# WD1M_BTLE_JDY-08.net
KiCad netlist of a schematic drawn in EAGLE
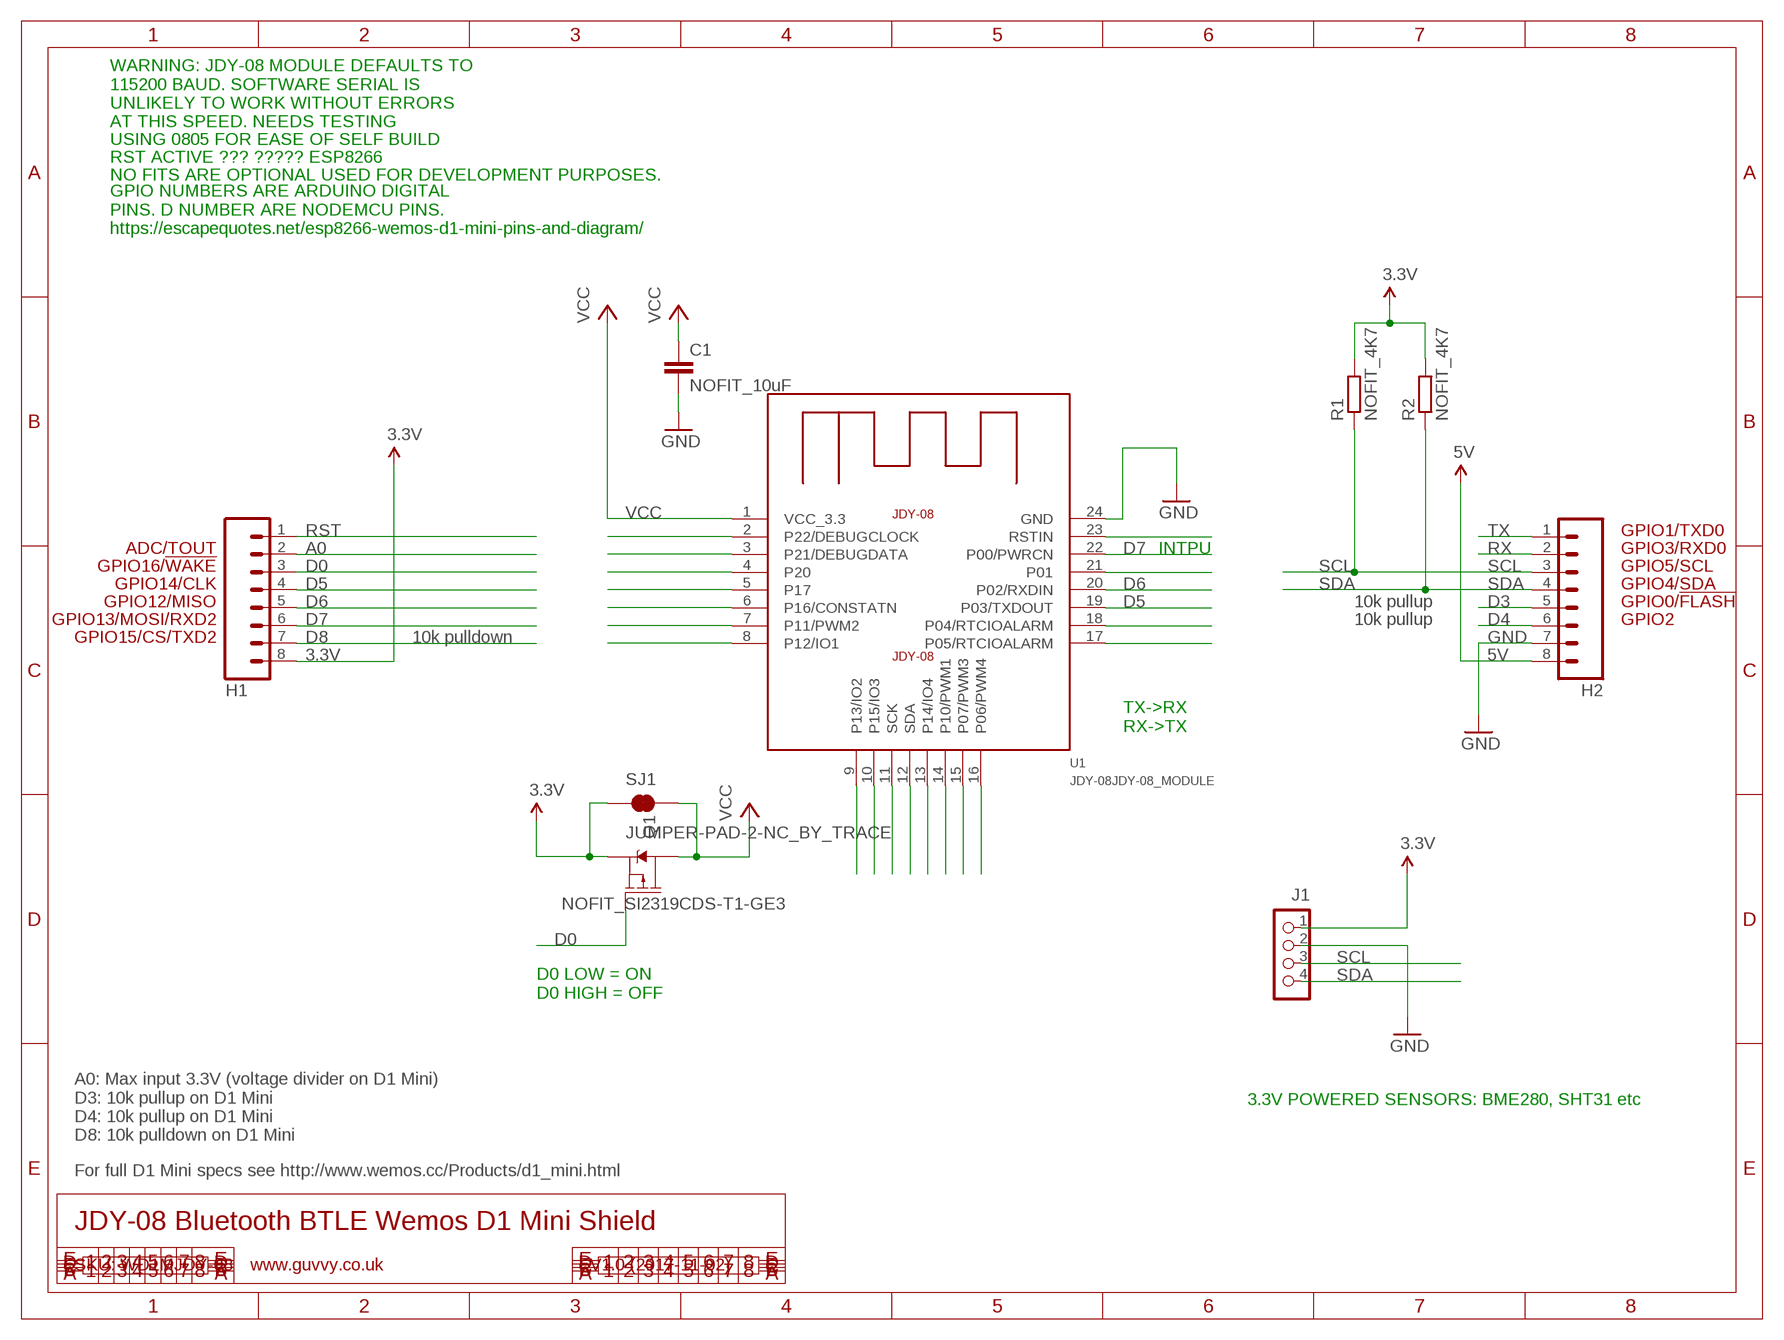
[diagram p0: schematic, sheet 1]

(export (version "E")
  (design (tool "Eeschema 10.0.6"))
  (components
    (comp (ref "C1")
      (value "NOFIT_10uF")
      (footprint "eagle-import:C0805K")
      (libsource (lib "eagle-import") (part "C-EUC0805K"))
    )
    (comp (ref "H1")
      (value "M08")
      (footprint "eagle-import:1X08")
      (libsource (lib "eagle-import") (part "M08"))
    )
    (comp (ref "H2")
      (value "M08")
      (footprint "eagle-import:1X08")
      (libsource (lib "eagle-import") (part "M08"))
    )
    (comp (ref "J1")
      (value "CON_HEADER_1X04")
      (footprint "eagle-import:M1X4")
      (libsource (lib "eagle-import") (part "CON_HEADER_1X04"))
    )
    (comp (ref "Q1")
      (value "NOFIT_SI2319CDS-T1-GE3")
      (footprint "eagle-import:SOT23-3")
      (libsource (lib "eagle-import") (part "MOSFET_PCH-IRLML2244"))
    )
    (comp (ref "R1")
      (value "NOFIT_4K7")
      (footprint "eagle-import:R0805")
      (libsource (lib "eagle-import") (part "R-EU_R0805"))
    )
    (comp (ref "R2")
      (value "NOFIT_4K7")
      (footprint "eagle-import:R0805")
      (libsource (lib "eagle-import") (part "R-EU_R0805"))
    )
    (comp (ref "SJ1")
      (value "JUMPER-PAD-2-NC_BY_TRACE")
      (footprint "eagle-import:PAD-JUMPER-2-NC_BY_TRACE_YES_SILK")
      (libsource (lib "eagle-import") (part "JUMPER-PAD-2-NC_BY_TRACE"))
    )
    (comp (ref "U1")
      (value "JDY-08JDY-08_MODULE")
      (footprint "eagle-import:JDY-08")
      (libsource (lib "eagle-import") (part "JDY-08JDY-08_MODULE"))
    )
  )
  (nets
    (net (code "1") (name "/A0") (class "Default")
      (node (ref "H1") (pin "2") (pinfunction "2_2") (pintype "passive"))
    )
    (net (code "2") (name "/D0") (class "Default")
      (node (ref "H1") (pin "3") (pinfunction "3_3") (pintype "passive"))
      (node (ref "Q1") (pin "1") (pinfunction "G_1") (pintype "bidirectional"))
    )
    (net (code "3") (name "/D3") (class "Default")
      (node (ref "H2") (pin "5") (pinfunction "5_5") (pintype "passive"))
    )
    (net (code "4") (name "/D4") (class "Default")
      (node (ref "H2") (pin "6") (pinfunction "6_6") (pintype "passive"))
    )
    (net (code "5") (name "/D5") (class "Default")
      (node (ref "H1") (pin "4") (pinfunction "4_4") (pintype "passive"))
      (node (ref "U1") (pin "19") (pinfunction "P03/TXDOUT_19") (pintype "bidirectional"))
    )
    (net (code "6") (name "/D6") (class "Default")
      (node (ref "H1") (pin "5") (pinfunction "5_5") (pintype "passive"))
      (node (ref "U1") (pin "20") (pinfunction "P02/RXDIN_20") (pintype "bidirectional"))
    )
    (net (code "7") (name "/D7") (class "Default")
      (node (ref "H1") (pin "6") (pinfunction "6_6") (pintype "passive"))
      (node (ref "U1") (pin "22") (pinfunction "P00/PWRCN_22") (pintype "bidirectional"))
    )
    (net (code "8") (name "/D8") (class "Default")
      (node (ref "H1") (pin "7") (pinfunction "7_7") (pintype "passive"))
    )
    (net (code "9") (name "/RST") (class "Default")
      (node (ref "H1") (pin "1") (pinfunction "1_1") (pintype "passive"))
    )
    (net (code "10") (name "/RX") (class "Default")
      (node (ref "H2") (pin "2") (pinfunction "2_2") (pintype "passive"))
    )
    (net (code "11") (name "/SCL") (class "Default")
      (node (ref "H2") (pin "3") (pinfunction "3_3") (pintype "passive"))
      (node (ref "J1") (pin "3") (pinfunction "3_3") (pintype "bidirectional"))
      (node (ref "R1") (pin "1") (pinfunction "1_1") (pintype "passive"))
    )
    (net (code "12") (name "/SDA") (class "Default")
      (node (ref "H2") (pin "4") (pinfunction "4_4") (pintype "passive"))
      (node (ref "J1") (pin "4") (pinfunction "4_4") (pintype "bidirectional"))
      (node (ref "R2") (pin "1") (pinfunction "1_1") (pintype "passive"))
    )
    (net (code "13") (name "/TX") (class "Default")
      (node (ref "H2") (pin "1") (pinfunction "1_1") (pintype "passive"))
    )
    (net (code "14") (name "3.3V") (class "Default")
      (node (ref "H1") (pin "8") (pinfunction "8_8") (pintype "passive"))
      (node (ref "J1") (pin "1") (pinfunction "1_1") (pintype "bidirectional"))
      (node (ref "Q1") (pin "2") (pinfunction "S_2") (pintype "bidirectional"))
      (node (ref "R1") (pin "2") (pinfunction "2_2") (pintype "passive"))
      (node (ref "R2") (pin "2") (pinfunction "2_2") (pintype "passive"))
      (node (ref "SJ1") (pin "1") (pinfunction "1_1") (pintype "passive"))
    )
    (net (code "15") (name "5V") (class "Default")
      (node (ref "H2") (pin "8") (pinfunction "8_8") (pintype "passive"))
    )
    (net (code "16") (name "GND") (class "Default")
      (node (ref "C1") (pin "2") (pinfunction "2_2") (pintype "passive"))
      (node (ref "H2") (pin "7") (pinfunction "7_7") (pintype "passive"))
      (node (ref "J1") (pin "2") (pinfunction "2_2") (pintype "bidirectional"))
      (node (ref "U1") (pin "24") (pinfunction "GND_24") (pintype "bidirectional"))
    )
    (net (code "17") (name "VCC") (class "Default")
      (node (ref "C1") (pin "1") (pinfunction "1_1") (pintype "passive"))
      (node (ref "Q1") (pin "3") (pinfunction "D_3") (pintype "bidirectional"))
      (node (ref "SJ1") (pin "2") (pinfunction "2_2") (pintype "passive"))
      (node (ref "U1") (pin "1") (pinfunction "VCC_3.3_1") (pintype "bidirectional"))
    )
    (net (code "18") (name "unconnected-(U1-P01-Pad21)") (class "Default")
      (node (ref "U1") (pin "21") (pinfunction "P01_21") (pintype "bidirectional"))
    )
    (net (code "19") (name "unconnected-(U1-P04{slash}RTCIOALARM-Pad18)") (class "Default")
      (node (ref "U1") (pin "18") (pinfunction "P04/RTCIOALARM_18") (pintype "bidirectional"))
    )
    (net (code "20") (name "unconnected-(U1-P05{slash}RTCIOALARM-Pad17)") (class "Default")
      (node (ref "U1") (pin "17") (pinfunction "P05/RTCIOALARM_17") (pintype "bidirectional"))
    )
    (net (code "21") (name "unconnected-(U1-P06{slash}PWM4-Pad16)") (class "Default")
      (node (ref "U1") (pin "16") (pinfunction "P06/PWM4_16") (pintype "bidirectional"))
    )
    (net (code "22") (name "unconnected-(U1-P07{slash}PWM3-Pad15)") (class "Default")
      (node (ref "U1") (pin "15") (pinfunction "P07/PWM3_15") (pintype "bidirectional"))
    )
    (net (code "23") (name "unconnected-(U1-P10{slash}PWM1-Pad14)") (class "Default")
      (node (ref "U1") (pin "14") (pinfunction "P10/PWM1_14") (pintype "bidirectional"))
    )
    (net (code "24") (name "unconnected-(U1-P11{slash}PWM2-Pad7)") (class "Default")
      (node (ref "U1") (pin "7") (pinfunction "P11/PWM2_7") (pintype "bidirectional"))
    )
    (net (code "25") (name "unconnected-(U1-P12{slash}IO1-Pad8)") (class "Default")
      (node (ref "U1") (pin "8") (pinfunction "P12/IO1_8") (pintype "bidirectional"))
    )
    (net (code "26") (name "unconnected-(U1-P13{slash}IO2-Pad9)") (class "Default")
      (node (ref "U1") (pin "9") (pinfunction "P13/IO2_9") (pintype "bidirectional"))
    )
    (net (code "27") (name "unconnected-(U1-P14{slash}IO4-Pad13)") (class "Default")
      (node (ref "U1") (pin "13") (pinfunction "P14/IO4_13") (pintype "bidirectional"))
    )
    (net (code "28") (name "unconnected-(U1-P15{slash}IO3-Pad10)") (class "Default")
      (node (ref "U1") (pin "10") (pinfunction "P15/IO3_10") (pintype "bidirectional"))
    )
    (net (code "29") (name "unconnected-(U1-P16{slash}CONSTATN-Pad6)") (class "Default")
      (node (ref "U1") (pin "6") (pinfunction "P16/CONSTATN_6") (pintype "bidirectional"))
    )
    (net (code "30") (name "unconnected-(U1-P17-Pad5)") (class "Default")
      (node (ref "U1") (pin "5") (pinfunction "P17_5") (pintype "bidirectional"))
    )
    (net (code "31") (name "unconnected-(U1-P20-Pad4)") (class "Default")
      (node (ref "U1") (pin "4") (pinfunction "P20_4") (pintype "bidirectional"))
    )
    (net (code "32") (name "unconnected-(U1-P21{slash}DEBUGDATA-Pad3)") (class "Default")
      (node (ref "U1") (pin "3") (pinfunction "P21/DEBUGDATA_3") (pintype "bidirectional"))
    )
    (net (code "33") (name "unconnected-(U1-P22{slash}DEBUGCLOCK-Pad2)") (class "Default")
      (node (ref "U1") (pin "2") (pinfunction "P22/DEBUGCLOCK_2") (pintype "bidirectional"))
    )
    (net (code "34") (name "unconnected-(U1-RSTIN-Pad23)") (class "Default")
      (node (ref "U1") (pin "23") (pinfunction "RSTIN_23") (pintype "bidirectional"))
    )
    (net (code "35") (name "unconnected-(U1-SCK-Pad11)") (class "Default")
      (node (ref "U1") (pin "11") (pinfunction "SCK_11") (pintype "bidirectional"))
    )
    (net (code "36") (name "unconnected-(U1-SDA-Pad12)") (class "Default")
      (node (ref "U1") (pin "12") (pinfunction "SDA_12") (pintype "bidirectional"))
    )
  )
)
